# 3Phase_Inverter1.net
KiCad netlist of a schematic drawn in Altium Designer
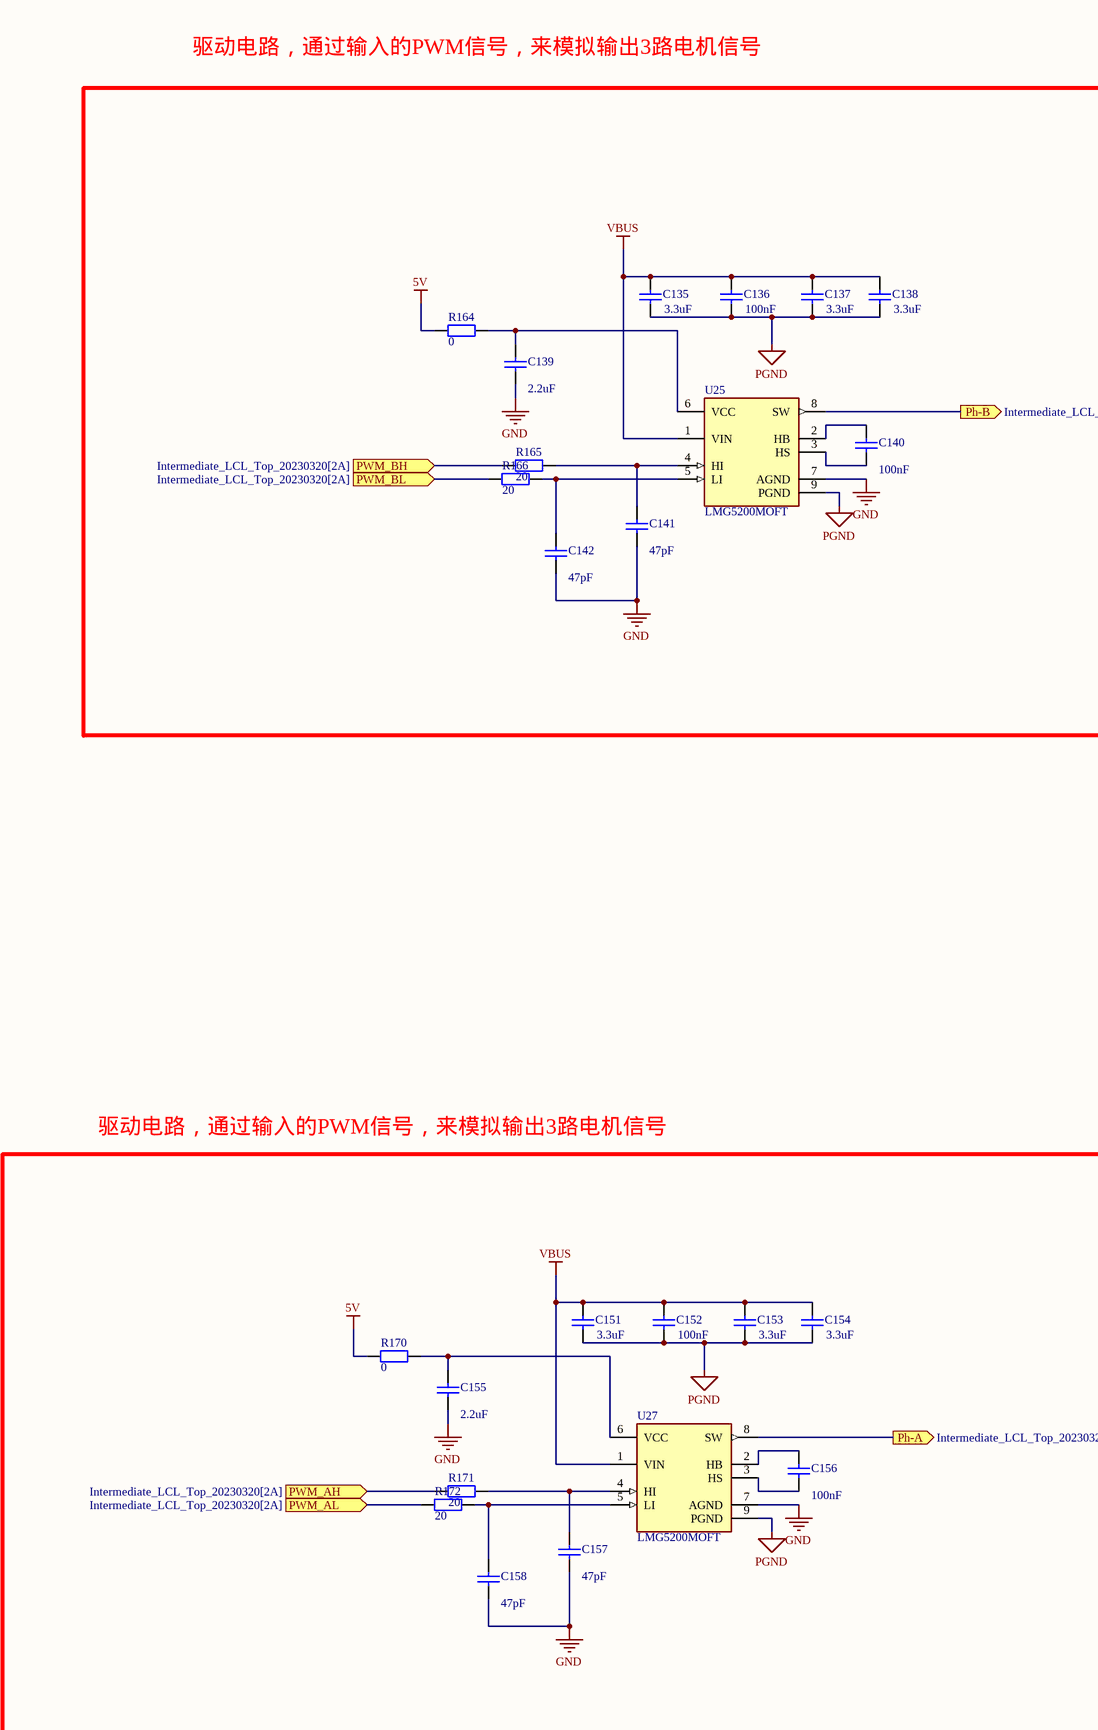
[diagram p0: 3Phase Inverter1.SchDoc, left]
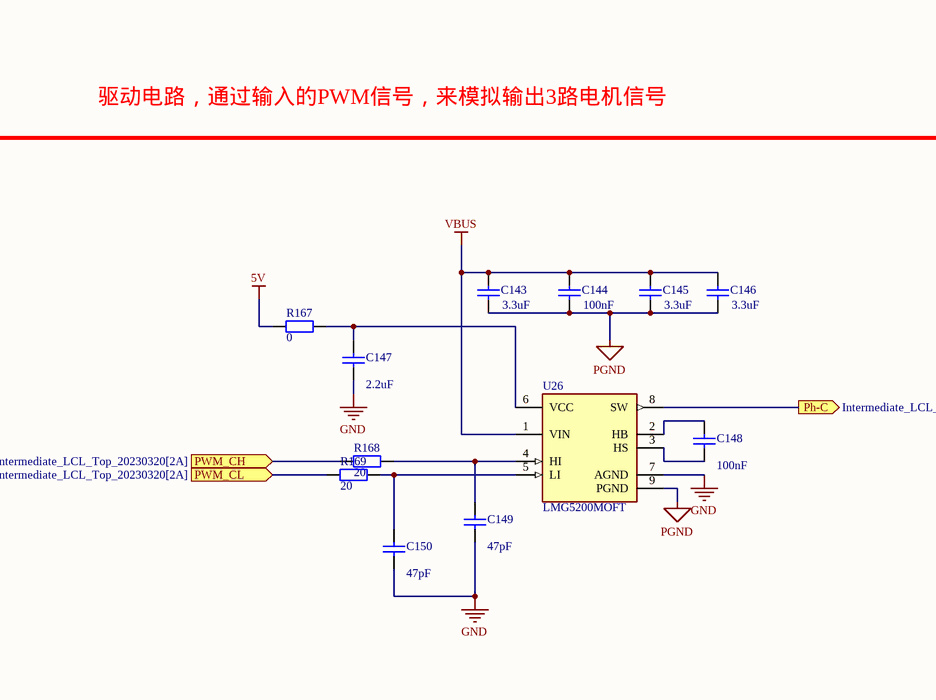
[diagram p1: 3Phase Inverter1.SchDoc, right]

(export (version "E")
  (design (tool "Eeschema 10.0.6"))
  (components
    (comp (ref "C135")
      (value "3.3uF")
      (footprint "CAPC1608X06N")
      (description "Capacitor")
      (fields (field (name "PUBLISHER") "Altium Limited"))
      (libsource (lib "aaa2") (part "Cap"))
    )
    (comp (ref "C136")
      (value "100nF")
      (footprint "CAPC1608X06N")
      (description "Capacitor")
      (fields (field (name "PUBLISHER") "Altium Limited"))
      (libsource (lib "Simscale") (part "Cap"))
    )
    (comp (ref "C137")
      (value "3.3uF")
      (footprint "CAPC1608X06N")
      (description "Capacitor")
      (fields (field (name "PUBLISHER") "Altium Limited"))
      (libsource (lib "Simscale") (part "Cap"))
    )
    (comp (ref "C138")
      (value "3.3uF")
      (footprint "CAPC1608X06N")
      (description "Capacitor")
      (fields (field (name "PUBLISHER") "Altium Limited"))
      (libsource (lib "Simscale") (part "Cap"))
    )
    (comp (ref "C139")
      (value "2.2uF")
      (footprint "CAPC1608X06N")
      (description "Capacitor")
      (fields (field (name "PUBLISHER") "Altium Limited"))
      (libsource (lib "Simscale") (part "Cap"))
    )
    (comp (ref "C140")
      (value "100nF")
      (footprint "CAPC1608X06N")
      (description "Capacitor")
      (fields (field (name "PUBLISHER") "Altium Limited"))
      (libsource (lib "Simscale") (part "Cap"))
    )
    (comp (ref "C141")
      (value "47pF")
      (footprint "CAPC1608X06N")
      (description "Capacitor")
      (fields (field (name "PUBLISHER") "Altium Limited"))
      (libsource (lib "Simscale") (part "Cap"))
    )
    (comp (ref "C142")
      (value "47pF")
      (footprint "CAPC1608X06N")
      (description "Capacitor")
      (fields (field (name "PUBLISHER") "Altium Limited"))
      (libsource (lib "Simscale") (part "Cap"))
    )
    (comp (ref "C143")
      (value "3.3uF")
      (footprint "CAPC1608X06N")
      (description "Capacitor")
      (fields (field (name "PUBLISHER") "Altium Limited"))
      (libsource (lib "aaa2") (part "Cap"))
    )
    (comp (ref "C144")
      (value "100nF")
      (footprint "CAPC1608X06N")
      (description "Capacitor")
      (fields (field (name "PUBLISHER") "Altium Limited"))
      (libsource (lib "Simscale") (part "Cap"))
    )
    (comp (ref "C145")
      (value "3.3uF")
      (footprint "CAPC1608X06N")
      (description "Capacitor")
      (fields (field (name "PUBLISHER") "Altium Limited"))
      (libsource (lib "Simscale") (part "Cap"))
    )
    (comp (ref "C146")
      (value "3.3uF")
      (footprint "CAPC1608X06N")
      (description "Capacitor")
      (fields (field (name "PUBLISHER") "Altium Limited"))
      (libsource (lib "Simscale") (part "Cap"))
    )
    (comp (ref "C147")
      (value "2.2uF")
      (footprint "CAPC1608X06N")
      (description "Capacitor")
      (fields (field (name "PUBLISHER") "Altium Limited"))
      (libsource (lib "Simscale") (part "Cap"))
    )
    (comp (ref "C148")
      (value "100nF")
      (footprint "CAPC1608X06N")
      (description "Capacitor")
      (fields (field (name "PUBLISHER") "Altium Limited"))
      (libsource (lib "Simscale") (part "Cap"))
    )
    (comp (ref "C149")
      (value "47pF")
      (footprint "CAPC1608X06N")
      (description "Capacitor")
      (fields (field (name "PUBLISHER") "Altium Limited"))
      (libsource (lib "Simscale") (part "Cap"))
    )
    (comp (ref "C150")
      (value "47pF")
      (footprint "CAPC1608X06N")
      (description "Capacitor")
      (fields (field (name "PUBLISHER") "Altium Limited"))
      (libsource (lib "Simscale") (part "Cap"))
    )
    (comp (ref "C151")
      (value "3.3uF")
      (footprint "CAPC1608X06N")
      (description "Capacitor")
      (fields (field (name "PUBLISHER") "Altium Limited"))
      (libsource (lib "aaa2") (part "Cap"))
    )
    (comp (ref "C152")
      (value "100nF")
      (footprint "CAPC1608X06N")
      (description "Capacitor")
      (fields (field (name "PUBLISHER") "Altium Limited"))
      (libsource (lib "Simscale") (part "Cap"))
    )
    (comp (ref "C153")
      (value "3.3uF")
      (footprint "CAPC1608X06N")
      (description "Capacitor")
      (fields (field (name "PUBLISHER") "Altium Limited"))
      (libsource (lib "Simscale") (part "Cap"))
    )
    (comp (ref "C154")
      (value "3.3uF")
      (footprint "CAPC1608X06N")
      (description "Capacitor")
      (fields (field (name "PUBLISHER") "Altium Limited"))
      (libsource (lib "Simscale") (part "Cap"))
    )
    (comp (ref "C155")
      (value "2.2uF")
      (footprint "CAPC1608X06N")
      (description "Capacitor")
      (fields (field (name "PUBLISHER") "Altium Limited"))
      (libsource (lib "Simscale") (part "Cap"))
    )
    (comp (ref "C156")
      (value "100nF")
      (footprint "CAPC1608X06N")
      (description "Capacitor")
      (fields (field (name "PUBLISHER") "Altium Limited"))
      (libsource (lib "Simscale") (part "Cap"))
    )
    (comp (ref "C157")
      (value "47pF")
      (footprint "CAPC1608X06N")
      (description "Capacitor")
      (fields (field (name "PUBLISHER") "Altium Limited"))
      (libsource (lib "Simscale") (part "Cap"))
    )
    (comp (ref "C158")
      (value "47pF")
      (footprint "CAPC1608X06N")
      (description "Capacitor")
      (fields (field (name "PUBLISHER") "Altium Limited"))
      (libsource (lib "Simscale") (part "Cap"))
    )
    (comp (ref "R164")
      (value "0")
      (footprint "RESC1608X05N")
      (description "贴片电阻")
      (libsource (lib "Simscale") (part "0603 100KΩ (1003) 1%_4"))
    )
    (comp (ref "R165")
      (value "20")
      (footprint "RESC1608X05N")
      (description "贴片电阻")
      (libsource (lib "Simscale") (part "0603 100KΩ (1003) 1%_4"))
    )
    (comp (ref "R166")
      (value "20")
      (footprint "RESC1608X05N")
      (description "贴片电阻")
      (libsource (lib "Simscale") (part "0603 100KΩ (1003) 1%_4"))
    )
    (comp (ref "R167")
      (value "0")
      (footprint "RESC1608X05N")
      (description "贴片电阻")
      (libsource (lib "Simscale") (part "0603 100KΩ (1003) 1%_4"))
    )
    (comp (ref "R168")
      (value "20")
      (footprint "RESC1608X05N")
      (description "贴片电阻")
      (libsource (lib "Simscale") (part "0603 100KΩ (1003) 1%_4"))
    )
    (comp (ref "R169")
      (value "20")
      (footprint "RESC1608X05N")
      (description "贴片电阻")
      (libsource (lib "Simscale") (part "0603 100KΩ (1003) 1%_4"))
    )
    (comp (ref "R170")
      (value "0")
      (footprint "RESC1608X05N")
      (description "贴片电阻")
      (libsource (lib "Simscale") (part "0603 100KΩ (1003) 1%_4"))
    )
    (comp (ref "R171")
      (value "20")
      (footprint "RESC1608X05N")
      (description "贴片电阻")
      (libsource (lib "Simscale") (part "0603 100KΩ (1003) 1%_4"))
    )
    (comp (ref "R172")
      (value "20")
      (footprint "RESC1608X05N")
      (description "贴片电阻")
      (libsource (lib "Simscale") (part "0603 100KΩ (1003) 1%_4"))
    )
    (comp (ref "U25")
      (value "LMG5200MOFT")
      (footprint "FP-MOF0009A-MFG")
      (description "None")
      (libsource (lib "Altium Content Vault") (part "e04ca9006c06531c2d1851f29eb7844"))
    )
    (comp (ref "U26")
      (value "LMG5200MOFT")
      (footprint "FP-MOF0009A-MFG")
      (description "None")
      (libsource (lib "Altium Content Vault") (part "e04ca9006c06531c2d1851f29eb7844"))
    )
    (comp (ref "U27")
      (value "LMG5200MOFT")
      (footprint "FP-MOF0009A-MFG")
      (description "None")
      (libsource (lib "Altium Content Vault") (part "e04ca9006c06531c2d1851f29eb7844"))
    )
  )
  (nets
    (net (code "1") (name "/PWM_AH") (class "Default")
      (node (ref "R171") (pin "2") (pinfunction "2_2") (pintype "passive"))
    )
    (net (code "2") (name "/PWM_AL") (class "Default")
      (node (ref "R172") (pin "2") (pinfunction "2_2") (pintype "passive"))
    )
    (net (code "3") (name "/PWM_BH") (class "Default")
      (node (ref "R165") (pin "2") (pinfunction "2_2") (pintype "passive"))
    )
    (net (code "4") (name "/PWM_BL") (class "Default")
      (node (ref "R166") (pin "2") (pinfunction "2_2") (pintype "passive"))
    )
    (net (code "5") (name "/PWM_CH") (class "Default")
      (node (ref "R168") (pin "2") (pinfunction "2_2") (pintype "passive"))
    )
    (net (code "6") (name "/PWM_CL") (class "Default")
      (node (ref "R169") (pin "2") (pinfunction "2_2") (pintype "passive"))
    )
    (net (code "7") (name "/Ph-A") (class "Default")
      (node (ref "U27") (pin "8") (pinfunction "SW_8") (pintype "output"))
    )
    (net (code "8") (name "/Ph-B") (class "Default")
      (node (ref "U25") (pin "8") (pinfunction "SW_8") (pintype "output"))
    )
    (net (code "9") (name "/Ph-C") (class "Default")
      (node (ref "U26") (pin "8") (pinfunction "SW_8") (pintype "output"))
    )
    (net (code "10") (name "5V") (class "Default")
      (node (ref "R164") (pin "2") (pinfunction "2_2") (pintype "passive"))
      (node (ref "R167") (pin "2") (pinfunction "2_2") (pintype "passive"))
      (node (ref "R170") (pin "2") (pinfunction "2_2") (pintype "passive"))
    )
    (net (code "11") (name "GND") (class "Default")
      (node (ref "C139") (pin "1") (pinfunction "1_1") (pintype "passive"))
      (node (ref "C141") (pin "2") (pinfunction "2_2") (pintype "passive"))
      (node (ref "C142") (pin "2") (pinfunction "2_2") (pintype "passive"))
      (node (ref "C147") (pin "1") (pinfunction "1_1") (pintype "passive"))
      (node (ref "C149") (pin "2") (pinfunction "2_2") (pintype "passive"))
      (node (ref "C150") (pin "2") (pinfunction "2_2") (pintype "passive"))
      (node (ref "C155") (pin "1") (pinfunction "1_1") (pintype "passive"))
      (node (ref "C157") (pin "2") (pinfunction "2_2") (pintype "passive"))
      (node (ref "C158") (pin "2") (pinfunction "2_2") (pintype "passive"))
      (node (ref "U25") (pin "7") (pinfunction "AGND_7") (pintype "power_in"))
      (node (ref "U26") (pin "7") (pinfunction "AGND_7") (pintype "power_in"))
      (node (ref "U27") (pin "7") (pinfunction "AGND_7") (pintype "power_in"))
    )
    (net (code "12") (name "Net-(U25-HB)") (class "Default")
      (node (ref "C140") (pin "1") (pinfunction "1_1") (pintype "passive"))
      (node (ref "U25") (pin "2") (pinfunction "HB_2") (pintype "passive"))
    )
    (net (code "13") (name "Net-(U25-HI)") (class "Default")
      (node (ref "C141") (pin "1") (pinfunction "1_1") (pintype "passive"))
      (node (ref "R165") (pin "1") (pinfunction "1_1") (pintype "passive"))
      (node (ref "U25") (pin "4") (pinfunction "HI_4") (pintype "input"))
    )
    (net (code "14") (name "Net-(U25-HS)") (class "Default")
      (node (ref "C140") (pin "2") (pinfunction "2_2") (pintype "passive"))
      (node (ref "U25") (pin "3") (pinfunction "HS_3") (pintype "passive"))
    )
    (net (code "15") (name "Net-(U25-LI)") (class "Default")
      (node (ref "C142") (pin "1") (pinfunction "1_1") (pintype "passive"))
      (node (ref "R166") (pin "1") (pinfunction "1_1") (pintype "passive"))
      (node (ref "U25") (pin "5") (pinfunction "LI_5") (pintype "input"))
    )
    (net (code "16") (name "Net-(U25-VCC)") (class "Default")
      (node (ref "C139") (pin "2") (pinfunction "2_2") (pintype "passive"))
      (node (ref "R164") (pin "1") (pinfunction "1_1") (pintype "passive"))
      (node (ref "U25") (pin "6") (pinfunction "VCC_6") (pintype "power_in"))
    )
    (net (code "17") (name "Net-(U26-HB)") (class "Default")
      (node (ref "C148") (pin "1") (pinfunction "1_1") (pintype "passive"))
      (node (ref "U26") (pin "2") (pinfunction "HB_2") (pintype "passive"))
    )
    (net (code "18") (name "Net-(U26-HI)") (class "Default")
      (node (ref "C149") (pin "1") (pinfunction "1_1") (pintype "passive"))
      (node (ref "R168") (pin "1") (pinfunction "1_1") (pintype "passive"))
      (node (ref "U26") (pin "4") (pinfunction "HI_4") (pintype "input"))
    )
    (net (code "19") (name "Net-(U26-HS)") (class "Default")
      (node (ref "C148") (pin "2") (pinfunction "2_2") (pintype "passive"))
      (node (ref "U26") (pin "3") (pinfunction "HS_3") (pintype "passive"))
    )
    (net (code "20") (name "Net-(U26-LI)") (class "Default")
      (node (ref "C150") (pin "1") (pinfunction "1_1") (pintype "passive"))
      (node (ref "R169") (pin "1") (pinfunction "1_1") (pintype "passive"))
      (node (ref "U26") (pin "5") (pinfunction "LI_5") (pintype "input"))
    )
    (net (code "21") (name "Net-(U26-VCC)") (class "Default")
      (node (ref "C147") (pin "2") (pinfunction "2_2") (pintype "passive"))
      (node (ref "R167") (pin "1") (pinfunction "1_1") (pintype "passive"))
      (node (ref "U26") (pin "6") (pinfunction "VCC_6") (pintype "power_in"))
    )
    (net (code "22") (name "Net-(U27-HB)") (class "Default")
      (node (ref "C156") (pin "1") (pinfunction "1_1") (pintype "passive"))
      (node (ref "U27") (pin "2") (pinfunction "HB_2") (pintype "passive"))
    )
    (net (code "23") (name "Net-(U27-HI)") (class "Default")
      (node (ref "C157") (pin "1") (pinfunction "1_1") (pintype "passive"))
      (node (ref "R171") (pin "1") (pinfunction "1_1") (pintype "passive"))
      (node (ref "U27") (pin "4") (pinfunction "HI_4") (pintype "input"))
    )
    (net (code "24") (name "Net-(U27-HS)") (class "Default")
      (node (ref "C156") (pin "2") (pinfunction "2_2") (pintype "passive"))
      (node (ref "U27") (pin "3") (pinfunction "HS_3") (pintype "passive"))
    )
    (net (code "25") (name "Net-(U27-LI)") (class "Default")
      (node (ref "C158") (pin "1") (pinfunction "1_1") (pintype "passive"))
      (node (ref "R172") (pin "1") (pinfunction "1_1") (pintype "passive"))
      (node (ref "U27") (pin "5") (pinfunction "LI_5") (pintype "input"))
    )
    (net (code "26") (name "Net-(U27-VCC)") (class "Default")
      (node (ref "C155") (pin "2") (pinfunction "2_2") (pintype "passive"))
      (node (ref "R170") (pin "1") (pinfunction "1_1") (pintype "passive"))
      (node (ref "U27") (pin "6") (pinfunction "VCC_6") (pintype "power_in"))
    )
    (net (code "27") (name "PGND") (class "Default")
      (node (ref "C135") (pin "1") (pinfunction "1_1") (pintype "passive"))
      (node (ref "C136") (pin "2") (pinfunction "2_2") (pintype "passive"))
      (node (ref "C137") (pin "1") (pinfunction "1_1") (pintype "passive"))
      (node (ref "C138") (pin "1") (pinfunction "1_1") (pintype "passive"))
      (node (ref "C143") (pin "1") (pinfunction "1_1") (pintype "passive"))
      (node (ref "C144") (pin "2") (pinfunction "2_2") (pintype "passive"))
      (node (ref "C145") (pin "1") (pinfunction "1_1") (pintype "passive"))
      (node (ref "C146") (pin "1") (pinfunction "1_1") (pintype "passive"))
      (node (ref "C151") (pin "1") (pinfunction "1_1") (pintype "passive"))
      (node (ref "C152") (pin "2") (pinfunction "2_2") (pintype "passive"))
      (node (ref "C153") (pin "1") (pinfunction "1_1") (pintype "passive"))
      (node (ref "C154") (pin "1") (pinfunction "1_1") (pintype "passive"))
      (node (ref "U25") (pin "9") (pinfunction "PGND_9") (pintype "power_in"))
      (node (ref "U26") (pin "9") (pinfunction "PGND_9") (pintype "power_in"))
      (node (ref "U27") (pin "9") (pinfunction "PGND_9") (pintype "power_in"))
    )
    (net (code "28") (name "VBUS") (class "Default")
      (node (ref "C135") (pin "2") (pinfunction "2_2") (pintype "passive"))
      (node (ref "C136") (pin "1") (pinfunction "1_1") (pintype "passive"))
      (node (ref "C137") (pin "2") (pinfunction "2_2") (pintype "passive"))
      (node (ref "C138") (pin "2") (pinfunction "2_2") (pintype "passive"))
      (node (ref "C143") (pin "2") (pinfunction "2_2") (pintype "passive"))
      (node (ref "C144") (pin "1") (pinfunction "1_1") (pintype "passive"))
      (node (ref "C145") (pin "2") (pinfunction "2_2") (pintype "passive"))
      (node (ref "C146") (pin "2") (pinfunction "2_2") (pintype "passive"))
      (node (ref "C151") (pin "2") (pinfunction "2_2") (pintype "passive"))
      (node (ref "C152") (pin "1") (pinfunction "1_1") (pintype "passive"))
      (node (ref "C153") (pin "2") (pinfunction "2_2") (pintype "passive"))
      (node (ref "C154") (pin "2") (pinfunction "2_2") (pintype "passive"))
      (node (ref "U25") (pin "1") (pinfunction "VIN_1") (pintype "power_in"))
      (node (ref "U26") (pin "1") (pinfunction "VIN_1") (pintype "power_in"))
      (node (ref "U27") (pin "1") (pinfunction "VIN_1") (pintype "power_in"))
    )
  )
)
